# ff555.net
KiCad netlist of a schematic drawn in EAGLE
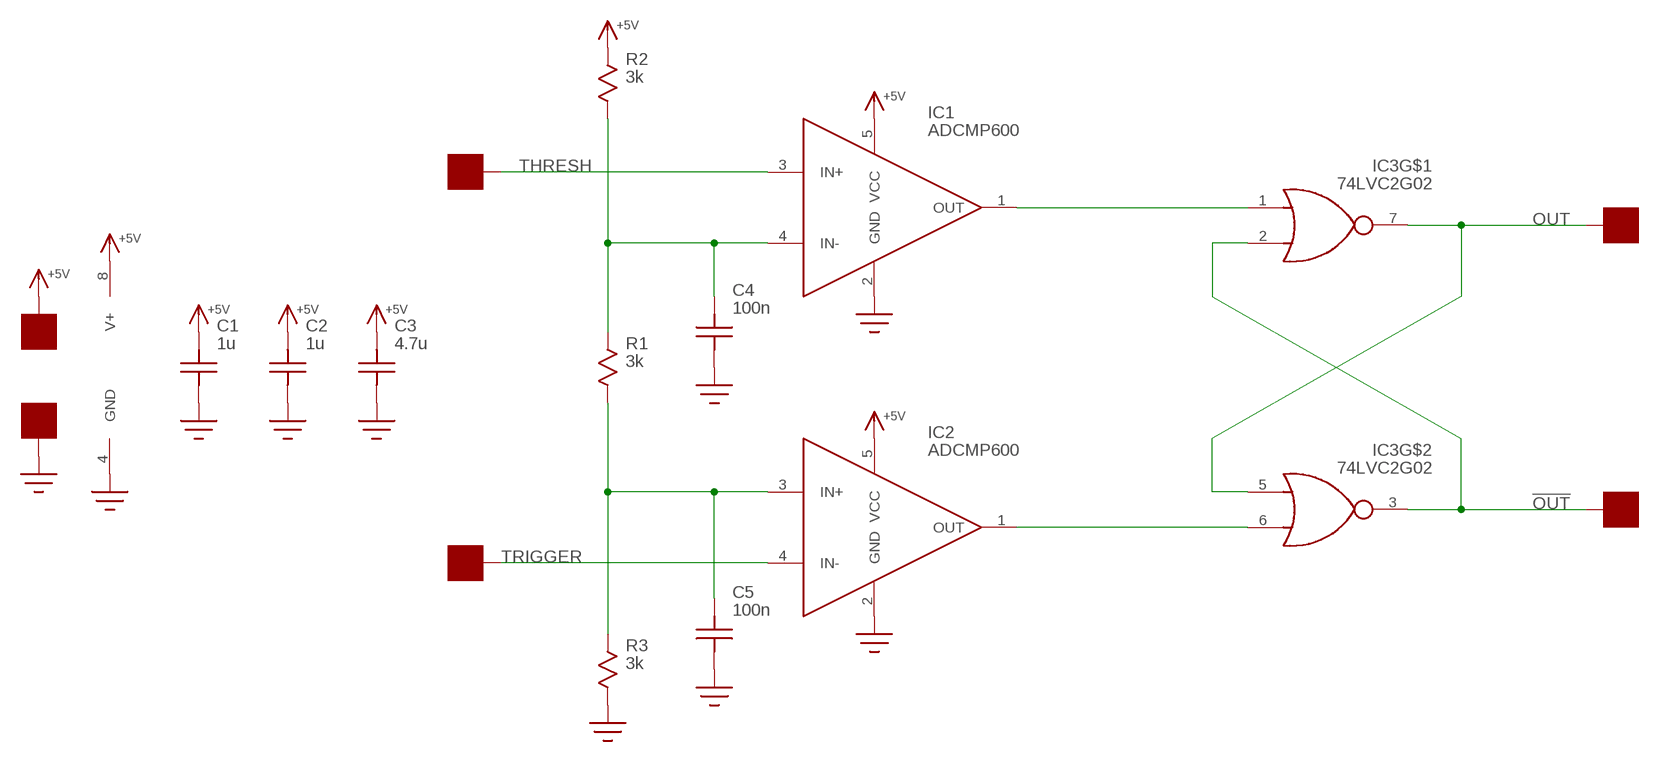
[diagram p0: schematic, sheet 1]

(export (version "E")
  (design (tool "Eeschema 10.0.6"))
  (components
    (comp (ref "C1")
      (value "1u")
      (footprint "eagle-import:C0603")
      (libsource (lib "eagle-import") (part "C0603"))
    )
    (comp (ref "C2")
      (value "1u")
      (footprint "eagle-import:C0603")
      (libsource (lib "eagle-import") (part "C0603"))
    )
    (comp (ref "C3")
      (value "4.7u")
      (footprint "eagle-import:0805")
      (libsource (lib "eagle-import") (part "C0805"))
    )
    (comp (ref "C4")
      (value "100n")
      (footprint "eagle-import:C0603")
      (libsource (lib "eagle-import") (part "C0603"))
    )
    (comp (ref "C5")
      (value "100n")
      (footprint "eagle-import:C0603")
      (libsource (lib "eagle-import") (part "C0603"))
    )
    (comp (ref "IC1")
      (value "ADCMP600")
      (footprint "eagle-import:SOT23-5")
      (libsource (lib "eagle-import") (part "ADCMP600"))
    )
    (comp (ref "IC2")
      (value "ADCMP600")
      (footprint "eagle-import:SOT23-5")
      (libsource (lib "eagle-import") (part "ADCMP600"))
    )
    (comp (ref "IC3")
      (value "74LVC2G02")
      (footprint "eagle-import:TSSOP8")
      (libsource (lib "eagle-import") (part "74LVC2G02"))
    )
    (comp (ref "R1")
      (value "3k")
      (footprint "eagle-import:R1206")
      (libsource (lib "eagle-import") (part "R1206"))
    )
    (comp (ref "R2")
      (value "3k")
      (footprint "eagle-import:R0603")
      (libsource (lib "eagle-import") (part "R0603"))
    )
    (comp (ref "R3")
      (value "3k")
      (footprint "eagle-import:R0603")
      (libsource (lib "eagle-import") (part "R0603"))
    )
    (comp (ref "U$15")
      (value "PAD100MIL")
      (footprint "eagle-import:PAD_100MIL")
      (libsource (lib "eagle-import") (part "PAD100MIL"))
    )
    (comp (ref "U$16")
      (value "PAD100MIL")
      (footprint "eagle-import:PAD_100MIL")
      (libsource (lib "eagle-import") (part "PAD100MIL"))
    )
    (comp (ref "U$17")
      (value "PAD100MIL")
      (footprint "eagle-import:PAD_100MIL")
      (libsource (lib "eagle-import") (part "PAD100MIL"))
    )
    (comp (ref "U$18")
      (value "PAD100MIL")
      (footprint "eagle-import:PAD_100MIL")
      (libsource (lib "eagle-import") (part "PAD100MIL"))
    )
    (comp (ref "U$19")
      (value "PAD100MIL")
      (footprint "eagle-import:PAD_100MIL")
      (libsource (lib "eagle-import") (part "PAD100MIL"))
    )
    (comp (ref "U$20")
      (value "PAD100MIL")
      (footprint "eagle-import:PAD_100MIL")
      (libsource (lib "eagle-import") (part "PAD100MIL"))
    )
  )
  (nets
    (net (code "1") (name "+5V") (class "Default")
      (node (ref "C1") (pin "P$2") (pinfunction "P$2_P$2") (pintype "bidirectional"))
      (node (ref "C2") (pin "P$2") (pinfunction "P$2_P$2") (pintype "bidirectional"))
      (node (ref "C3") (pin "P$2") (pinfunction "P$2_P$2") (pintype "bidirectional"))
      (node (ref "IC1") (pin "5") (pinfunction "VCC_5") (pintype "bidirectional"))
      (node (ref "IC2") (pin "5") (pinfunction "VCC_5") (pintype "bidirectional"))
      (node (ref "IC3") (pin "8") (pinfunction "V+_8") (pintype "bidirectional"))
      (node (ref "R2") (pin "P$1") (pinfunction "P$3_P$1") (pintype "bidirectional"))
      (node (ref "U$15") (pin "P$1") (pinfunction "P$1_P$1") (pintype "bidirectional"))
    )
    (net (code "2") (name "/OUT") (class "Default")
      (node (ref "IC3") (pin "5") (pinfunction "A_5") (pintype "bidirectional"))
      (node (ref "IC3") (pin "7") (pinfunction "Y_7") (pintype "bidirectional"))
      (node (ref "U$19") (pin "P$1") (pinfunction "P$1_P$1") (pintype "bidirectional"))
    )
    (net (code "3") (name "/THRESH") (class "Default")
      (node (ref "IC1") (pin "3") (pinfunction "IN+_3") (pintype "bidirectional"))
      (node (ref "U$17") (pin "P$1") (pinfunction "P$1_P$1") (pintype "bidirectional"))
    )
    (net (code "4") (name "/TRIGGER") (class "Default")
      (node (ref "IC2") (pin "4") (pinfunction "IN-_4") (pintype "bidirectional"))
      (node (ref "U$18") (pin "P$1") (pinfunction "P$1_P$1") (pintype "bidirectional"))
    )
    (net (code "5") (name "/~{OUT}") (class "Default")
      (node (ref "IC3") (pin "2") (pinfunction "B_2") (pintype "bidirectional"))
      (node (ref "IC3") (pin "3") (pinfunction "Y_3") (pintype "bidirectional"))
      (node (ref "U$20") (pin "P$1") (pinfunction "P$1_P$1") (pintype "bidirectional"))
    )
    (net (code "6") (name "GND") (class "Default")
      (node (ref "C1") (pin "P$1") (pinfunction "P$1_P$1") (pintype "bidirectional"))
      (node (ref "C2") (pin "P$1") (pinfunction "P$1_P$1") (pintype "bidirectional"))
      (node (ref "C3") (pin "P$1") (pinfunction "P$1_P$1") (pintype "bidirectional"))
      (node (ref "C4") (pin "P$1") (pinfunction "P$1_P$1") (pintype "bidirectional"))
      (node (ref "C5") (pin "P$1") (pinfunction "P$1_P$1") (pintype "bidirectional"))
      (node (ref "IC1") (pin "2") (pinfunction "GND_2") (pintype "bidirectional"))
      (node (ref "IC2") (pin "2") (pinfunction "GND_2") (pintype "bidirectional"))
      (node (ref "IC3") (pin "4") (pinfunction "GND_4") (pintype "bidirectional"))
      (node (ref "R3") (pin "P$2") (pinfunction "P$4_P$2") (pintype "bidirectional"))
      (node (ref "U$16") (pin "P$1") (pinfunction "P$1_P$1") (pintype "bidirectional"))
    )
    (net (code "7") (name "Net-(IC1-IN-)") (class "Default")
      (node (ref "C4") (pin "P$2") (pinfunction "P$2_P$2") (pintype "bidirectional"))
      (node (ref "IC1") (pin "4") (pinfunction "IN-_4") (pintype "bidirectional"))
      (node (ref "R1") (pin "P$1") (pinfunction "P$3_P$1") (pintype "bidirectional"))
      (node (ref "R2") (pin "P$2") (pinfunction "P$4_P$2") (pintype "bidirectional"))
    )
    (net (code "8") (name "Net-(IC1-OUT)") (class "Default")
      (node (ref "IC1") (pin "1") (pinfunction "OUT_1") (pintype "bidirectional"))
      (node (ref "IC3") (pin "1") (pinfunction "A_1") (pintype "bidirectional"))
    )
    (net (code "9") (name "Net-(IC2-IN+)") (class "Default")
      (node (ref "C5") (pin "P$2") (pinfunction "P$2_P$2") (pintype "bidirectional"))
      (node (ref "IC2") (pin "3") (pinfunction "IN+_3") (pintype "bidirectional"))
      (node (ref "R1") (pin "P$2") (pinfunction "P$4_P$2") (pintype "bidirectional"))
      (node (ref "R3") (pin "P$1") (pinfunction "P$3_P$1") (pintype "bidirectional"))
    )
    (net (code "10") (name "Net-(IC2-OUT)") (class "Default")
      (node (ref "IC2") (pin "1") (pinfunction "OUT_1") (pintype "bidirectional"))
      (node (ref "IC3") (pin "6") (pinfunction "B_6") (pintype "bidirectional"))
    )
  )
)
